# Card_Interface.net
KiCad netlist of a schematic drawn in Altium Designer
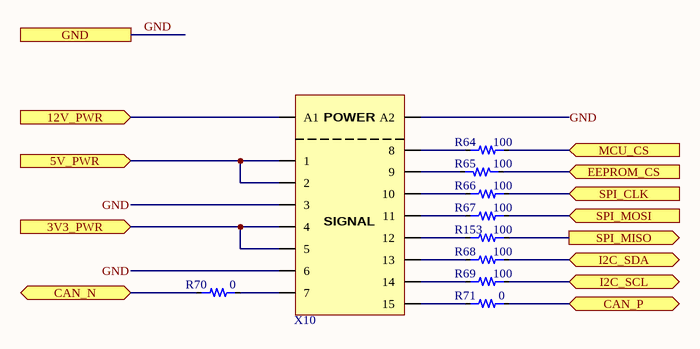
[diagram p0: Card_Interface.SchDoc]

(export (version "E")
  (design (tool "Eeschema 10.0.6"))
  (components
    (comp (ref "R64")
      (value "100")
      (footprint "0603_RES")
      (fields (field (name "Comment") "Resistor"))
      (libsource (lib "Resistors") (part "Resistor"))
    )
    (comp (ref "R65")
      (value "100")
      (footprint "0603_RES")
      (fields (field (name "Comment") "Resistor"))
      (libsource (lib "Resistors") (part "Resistor"))
    )
    (comp (ref "R66")
      (value "100")
      (footprint "0603_RES")
      (fields (field (name "Comment") "Resistor"))
      (libsource (lib "Resistors") (part "Resistor"))
    )
    (comp (ref "R67")
      (value "100")
      (footprint "0603_RES")
      (fields (field (name "Comment") "Resistor"))
      (libsource (lib "Resistors") (part "Resistor"))
    )
    (comp (ref "R68")
      (value "100")
      (footprint "0603_RES")
      (fields (field (name "Comment") "Resistor"))
      (libsource (lib "Resistors") (part "Resistor"))
    )
    (comp (ref "R69")
      (value "100")
      (footprint "0603_RES")
      (fields (field (name "Comment") "Resistor"))
      (libsource (lib "Resistors") (part "Resistor"))
    )
    (comp (ref "R70")
      (value "0")
      (footprint "0603_RES")
      (fields (field (name "Comment") "Resistor"))
      (libsource (lib "Resistors") (part "Resistor"))
    )
    (comp (ref "R71")
      (value "0")
      (footprint "0603_RES")
      (fields (field (name "Comment") "Resistor"))
      (libsource (lib "Resistors") (part "Resistor"))
    )
    (comp (ref "R153")
      (value "100")
      (footprint "0603_RES")
      (fields (field (name "Comment") "Resistor"))
      (libsource (lib "Resistors") (part "Resistor"))
    )
    (comp (ref "X10")
      (value "681M17W2203L")
      (footprint "681M17W2203L")
      (description "17 (15 + 2 Power) Position D-Sub, Combo Receptacle, Female Sockets Connector")
      (libsource (lib "Connectors") (part "681M17W2203L"))
    )
  )
  (nets
    (net (code "1") (name "/3V3_PWR") (class "Default")
      (node (ref "X10") (pin "4") (pinfunction "4_4") (pintype "passive"))
      (node (ref "X10") (pin "5") (pinfunction "5_5") (pintype "passive"))
    )
    (net (code "2") (name "/5V_PWR") (class "Default")
      (node (ref "X10") (pin "1") (pinfunction "1_1") (pintype "passive"))
      (node (ref "X10") (pin "2") (pinfunction "2_2") (pintype "passive"))
    )
    (net (code "3") (name "/12V_PWR") (class "Default")
      (node (ref "X10") (pin "A1") (pinfunction "A1_A1") (pintype "passive"))
    )
    (net (code "4") (name "/CAN_N") (class "Default")
      (node (ref "R70") (pin "1") (pinfunction "1_1") (pintype "passive"))
    )
    (net (code "5") (name "/CAN_P") (class "Default")
      (node (ref "R71") (pin "1") (pinfunction "1_1") (pintype "passive"))
    )
    (net (code "6") (name "/EEPROM_CS") (class "Default")
      (node (ref "R65") (pin "2") (pinfunction "2_2") (pintype "passive"))
    )
    (net (code "7") (name "/GND") (class "Default")
      (node (ref "X10") (pin "3") (pinfunction "3_3") (pintype "passive"))
      (node (ref "X10") (pin "6") (pinfunction "6_6") (pintype "passive"))
      (node (ref "X10") (pin "A2") (pinfunction "A2_A2") (pintype "passive"))
    )
    (net (code "8") (name "/I2C_SCL") (class "Default")
      (node (ref "R69") (pin "1") (pinfunction "1_1") (pintype "passive"))
    )
    (net (code "9") (name "/I2C_SDA") (class "Default")
      (node (ref "R68") (pin "1") (pinfunction "1_1") (pintype "passive"))
    )
    (net (code "10") (name "/MCU_CS") (class "Default")
      (node (ref "R64") (pin "1") (pinfunction "1_1") (pintype "passive"))
    )
    (net (code "11") (name "/SPI_CLK") (class "Default")
      (node (ref "R66") (pin "1") (pinfunction "1_1") (pintype "passive"))
    )
    (net (code "12") (name "/SPI_MISO") (class "Default")
      (node (ref "R153") (pin "1") (pinfunction "1_1") (pintype "passive"))
    )
    (net (code "13") (name "/SPI_MOSI") (class "Default")
      (node (ref "R67") (pin "1") (pinfunction "1_1") (pintype "passive"))
    )
    (net (code "14") (name "Net-(R64-Pad2)") (class "Default")
      (node (ref "R64") (pin "2") (pinfunction "2_2") (pintype "passive"))
      (node (ref "X10") (pin "8") (pinfunction "8_8") (pintype "passive"))
    )
    (net (code "15") (name "Net-(R65-Pad1)") (class "Default")
      (node (ref "R65") (pin "1") (pinfunction "1_1") (pintype "passive"))
      (node (ref "X10") (pin "9") (pinfunction "9_9") (pintype "passive"))
    )
    (net (code "16") (name "Net-(R66-Pad2)") (class "Default")
      (node (ref "R66") (pin "2") (pinfunction "2_2") (pintype "passive"))
      (node (ref "X10") (pin "10") (pinfunction "10_10") (pintype "passive"))
    )
    (net (code "17") (name "Net-(R67-Pad2)") (class "Default")
      (node (ref "R67") (pin "2") (pinfunction "2_2") (pintype "passive"))
      (node (ref "X10") (pin "11") (pinfunction "11_11") (pintype "passive"))
    )
    (net (code "18") (name "Net-(R68-Pad2)") (class "Default")
      (node (ref "R68") (pin "2") (pinfunction "2_2") (pintype "passive"))
      (node (ref "X10") (pin "13") (pinfunction "13_13") (pintype "passive"))
    )
    (net (code "19") (name "Net-(R69-Pad2)") (class "Default")
      (node (ref "R69") (pin "2") (pinfunction "2_2") (pintype "passive"))
      (node (ref "X10") (pin "14") (pinfunction "14_14") (pintype "passive"))
    )
    (net (code "20") (name "Net-(R70-Pad2)") (class "Default")
      (node (ref "R70") (pin "2") (pinfunction "2_2") (pintype "passive"))
      (node (ref "X10") (pin "7") (pinfunction "7_7") (pintype "passive"))
    )
    (net (code "21") (name "Net-(R71-Pad2)") (class "Default")
      (node (ref "R71") (pin "2") (pinfunction "2_2") (pintype "passive"))
      (node (ref "X10") (pin "15") (pinfunction "15_15") (pintype "passive"))
    )
    (net (code "22") (name "Net-(R153-Pad2)") (class "Default")
      (node (ref "R153") (pin "2") (pinfunction "2_2") (pintype "passive"))
      (node (ref "X10") (pin "12") (pinfunction "12_12") (pintype "passive"))
    )
  )
)
